# 3S_10A_BMS.net
KiCad netlist of a schematic drawn in EasyEDA
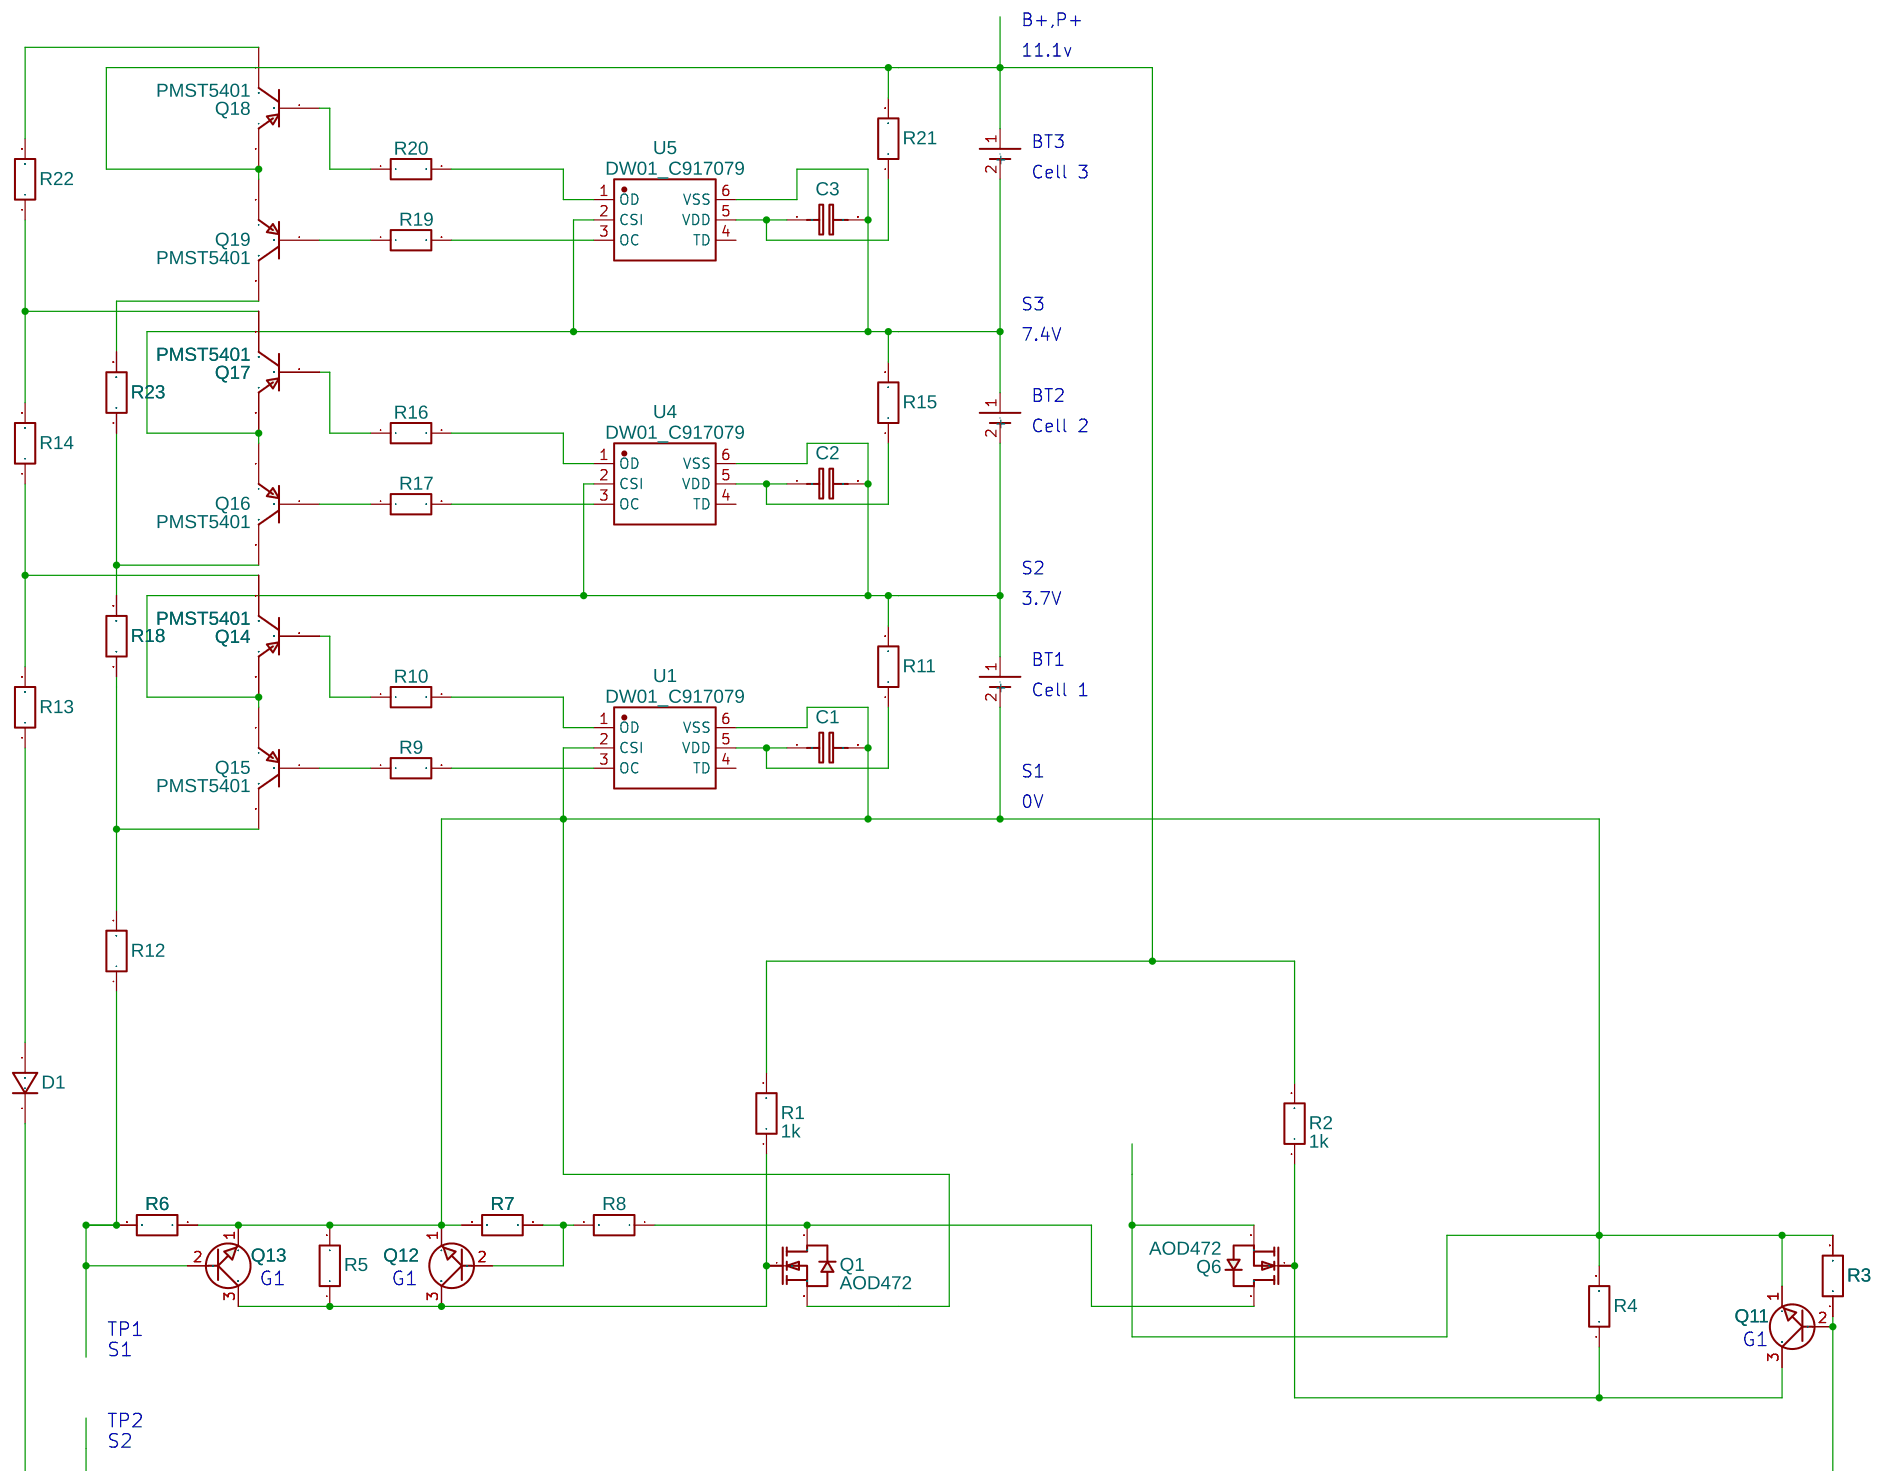
[diagram p0: 3s 10A Schematic]
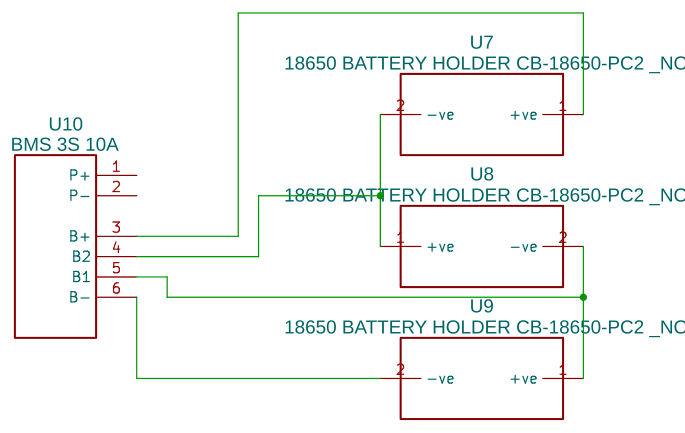
[diagram p1: 12v connection]

(export (version "E")
  (design (tool "Eeschema 10.0.6"))
  (components
    (comp (ref "C1") (value "0.1u") (libsource (lib "") (part "C_0603_EU")))
    (comp (ref "C2") (value "0.1u") (libsource (lib "") (part "C_0603_EU")))
    (comp (ref "C3") (value "0.1u") (libsource (lib "") (part "C_0603_EU")))
    (comp (ref "D1")
      (value "1N4007W")
      (fields (field (name "BOM_Supplier Part") "C328592"))
      (libsource (lib "") (part "1N4007W"))
    )
    (comp (ref "Q1")
      (value "AOD472")
      (fields (field (name "BOM_Supplier Part") "C693172"))
      (libsource (lib "") (part "AOD472"))
    )
    (comp (ref "Q6")
      (value "AOD472")
      (fields (field (name "BOM_Supplier Part") "C693172"))
      (libsource (lib "") (part "AOD472_1"))
    )
    (comp (ref "Q11") (value "2N2222") (libsource (lib "") (part "2N2222_1")))
    (comp (ref "Q12") (value "2N2222") (libsource (lib "") (part "2N2222_1")))
    (comp (ref "Q13") (value "2N2222") (libsource (lib "") (part "2N2222")))
    (comp (ref "Q14") (value "PMST5401") (libsource (lib "") (part "PMST5401")))
    (comp (ref "Q15") (value "PMST5401") (libsource (lib "") (part "PMST5401_1")))
    (comp (ref "Q16") (value "PMST5401") (libsource (lib "") (part "PMST5401_1")))
    (comp (ref "Q17") (value "PMST5401") (libsource (lib "") (part "PMST5401")))
    (comp (ref "Q18") (value "PMST5401") (libsource (lib "") (part "PMST5401")))
    (comp (ref "Q19") (value "PMST5401") (libsource (lib "") (part "PMST5401_1")))
    (comp (ref "R1") (value "1k") (libsource (lib "") (part "R_0603_EU")))
    (comp (ref "R2") (value "1k") (libsource (lib "") (part "R_0603_EU")))
    (comp (ref "R3") (value "1k") (libsource (lib "") (part "R_0603_EU")))
    (comp (ref "R4") (value "1k") (libsource (lib "") (part "R_0603_EU")))
    (comp (ref "R5") (value "1k") (libsource (lib "") (part "R_0603_EU")))
    (comp (ref "R6") (value "1k") (libsource (lib "") (part "R_0603_EU_1")))
    (comp (ref "R7") (value "1k") (libsource (lib "") (part "R_0603_EU_1")))
    (comp (ref "R8") (value "1k") (libsource (lib "") (part "R_0603_EU_1")))
    (comp (ref "R9") (value "1k") (libsource (lib "") (part "R_0603_EU_2")))
    (comp (ref "R10") (value "1k") (libsource (lib "") (part "R_0603_EU_2")))
    (comp (ref "R11") (value "1k") (libsource (lib "") (part "R_0603_EU")))
    (comp (ref "R12") (value "1k") (libsource (lib "") (part "R_0603_EU")))
    (comp (ref "R13") (value "1k") (libsource (lib "") (part "R_0603_EU")))
    (comp (ref "R14") (value "1k") (libsource (lib "") (part "R_0603_EU")))
    (comp (ref "R15") (value "1k") (libsource (lib "") (part "R_0603_EU")))
    (comp (ref "R16") (value "1k") (libsource (lib "") (part "R_0603_EU_2")))
    (comp (ref "R17") (value "1k") (libsource (lib "") (part "R_0603_EU_2")))
    (comp (ref "R18") (value "1k") (libsource (lib "") (part "R_0603_EU")))
    (comp (ref "R19") (value "1k") (libsource (lib "") (part "R_0603_EU_2")))
    (comp (ref "R20") (value "1k") (libsource (lib "") (part "R_0603_EU_2")))
    (comp (ref "R21") (value "1k") (libsource (lib "") (part "R_0603_EU")))
    (comp (ref "R22") (value "1k") (libsource (lib "") (part "R_0603_EU")))
    (comp (ref "R23") (value "1k") (libsource (lib "") (part "R_0603_EU")))
    (comp (ref "U1")
      (value "DW01_C917079")
      (fields (field (name "BOM_Manufacturer Part") "DW01") (field (name "BOM_Supplier Part") "C917079"))
      (libsource (lib "") (part "DW01_C917079"))
    )
    (comp (ref "U2") (value "Li-ion battery") (libsource (lib "") (part "Li-ion battery")))
    (comp (ref "U3") (value "Li-ion battery") (libsource (lib "") (part "Li-ion battery")))
    (comp (ref "U4")
      (value "DW01_C917079")
      (fields (field (name "BOM_Manufacturer Part") "DW01") (field (name "BOM_Supplier Part") "C917079"))
      (libsource (lib "") (part "DW01_C917079"))
    )
    (comp (ref "U5")
      (value "DW01_C917079")
      (fields (field (name "BOM_Manufacturer Part") "DW01") (field (name "BOM_Supplier Part") "C917079"))
      (libsource (lib "") (part "DW01_C917079"))
    )
    (comp (ref "U6") (value "Li-ion battery") (libsource (lib "") (part "Li-ion battery")))
    (comp (ref "U7")
      (value "18650 BATTERY HOLDER CB-18650-PC2 _NOTEMP COPY")
      (libsource (lib "") (part "18650 BATTERY HOLDER CB-18650-PC2 _NOTEMP COPY_1"))
    )
    (comp (ref "U8")
      (value "18650 BATTERY HOLDER CB-18650-PC2 _NOTEMP COPY")
      (libsource (lib "") (part "18650 BATTERY HOLDER CB-18650-PC2 _NOTEMP COPY"))
    )
    (comp (ref "U9")
      (value "18650 BATTERY HOLDER CB-18650-PC2 _NOTEMP COPY")
      (libsource (lib "") (part "18650 BATTERY HOLDER CB-18650-PC2 _NOTEMP COPY_1"))
    )
    (comp (ref "U10") (value "BMS 3S 10A") (libsource (lib "") (part "BMS 3S 10A")))
  )
  (nets
    (net (code "1") (name "Net-(D1-Pad2)") (class "Default")
      (node (ref "D1") (pin "2") (pinfunction "2_2") (pintype "unspecified"))
      (node (ref "R13") (pin "1") (pinfunction "1_1") (pintype "unspecified"))
    )
    (net (code "2") (name "Net-(Q1-D)") (class "Default")
      (node (ref "Q1") (pin "2") (pinfunction "D_2") (pintype "unspecified"))
      (node (ref "Q6") (pin "2") (pinfunction "D_2") (pintype "unspecified"))
      (node (ref "R8") (pin "1") (pinfunction "1_1") (pintype "unspecified"))
    )
    (net (code "3") (name "Net-(Q1-G)") (class "Default")
      (node (ref "Q1") (pin "1") (pinfunction "G_1") (pintype "unspecified"))
      (node (ref "Q12") (pin "3") (pinfunction "C_3") (pintype "unspecified"))
      (node (ref "Q13") (pin "3") (pinfunction "C_3") (pintype "unspecified"))
      (node (ref "R1") (pin "1") (pinfunction "1_1") (pintype "unspecified"))
      (node (ref "R5") (pin "1") (pinfunction "1_1") (pintype "unspecified"))
    )
    (net (code "4") (name "Net-(Q1-S)") (class "Default")
      (node (ref "C1") (pin "2") (pinfunction "2_2") (pintype "unspecified"))
      (node (ref "Q1") (pin "3") (pinfunction "S_3") (pintype "unspecified"))
      (node (ref "Q11") (pin "1") (pinfunction "E_1") (pintype "unspecified"))
      (node (ref "Q12") (pin "1") (pinfunction "E_1") (pintype "unspecified"))
      (node (ref "Q13") (pin "1") (pinfunction "E_1") (pintype "unspecified"))
      (node (ref "Q6") (pin "3") (pinfunction "S_3") (pintype "unspecified"))
      (node (ref "R3") (pin "2") (pinfunction "2_2") (pintype "unspecified"))
      (node (ref "R4") (pin "2") (pinfunction "2_2") (pintype "unspecified"))
      (node (ref "R5") (pin "2") (pinfunction "2_2") (pintype "unspecified"))
      (node (ref "R6") (pin "1") (pinfunction "1_1") (pintype "unspecified"))
      (node (ref "R7") (pin "2") (pinfunction "2_2") (pintype "unspecified"))
      (node (ref "U1") (pin "2") (pinfunction "CSI_2") (pintype "unspecified"))
      (node (ref "U1") (pin "6") (pinfunction "VSS_6") (pintype "unspecified"))
      (node (ref "U2") (pin "2") (pinfunction "-_2") (pintype "unspecified"))
    )
    (net (code "5") (name "Net-(Q11-B)") (class "Default")
      (node (ref "D1") (pin "1") (pinfunction "1_1") (pintype "unspecified"))
      (node (ref "Q11") (pin "2") (pinfunction "B_2") (pintype "input"))
      (node (ref "R3") (pin "1") (pinfunction "1_1") (pintype "unspecified"))
    )
    (net (code "6") (name "Net-(Q11-C)") (class "Default")
      (node (ref "Q11") (pin "3") (pinfunction "C_3") (pintype "unspecified"))
      (node (ref "Q6") (pin "1") (pinfunction "G_1") (pintype "unspecified"))
      (node (ref "R2") (pin "1") (pinfunction "1_1") (pintype "unspecified"))
      (node (ref "R4") (pin "1") (pinfunction "1_1") (pintype "unspecified"))
    )
    (net (code "7") (name "Net-(Q12-B)") (class "Default")
      (node (ref "Q12") (pin "2") (pinfunction "B_2") (pintype "input"))
      (node (ref "R7") (pin "1") (pinfunction "1_1") (pintype "unspecified"))
      (node (ref "R8") (pin "2") (pinfunction "2_2") (pintype "unspecified"))
    )
    (net (code "8") (name "Net-(Q13-B)") (class "Default")
      (node (ref "Q13") (pin "2") (pinfunction "B_2") (pintype "input"))
      (node (ref "R12") (pin "1") (pinfunction "1_1") (pintype "unspecified"))
      (node (ref "R6") (pin "2") (pinfunction "2_2") (pintype "unspecified"))
    )
    (net (code "9") (name "Net-(Q14-B)") (class "Default")
      (node (ref "Q14") (pin "1") (pinfunction "B_1") (pintype "unspecified"))
      (node (ref "R10") (pin "1") (pinfunction "1_1") (pintype "unspecified"))
    )
    (net (code "10") (name "Net-(Q14-C)") (class "Default")
      (node (ref "Q14") (pin "3") (pinfunction "C_3") (pintype "unspecified"))
      (node (ref "R13") (pin "2") (pinfunction "2_2") (pintype "unspecified"))
      (node (ref "R14") (pin "1") (pinfunction "1_1") (pintype "unspecified"))
    )
    (net (code "11") (name "Net-(Q14-E)") (class "Default")
      (node (ref "C2") (pin "2") (pinfunction "2_2") (pintype "unspecified"))
      (node (ref "Q14") (pin "2") (pinfunction "E_2") (pintype "unspecified"))
      (node (ref "Q15") (pin "2") (pinfunction "E_2") (pintype "unspecified"))
      (node (ref "R11") (pin "2") (pinfunction "2_2") (pintype "unspecified"))
      (node (ref "U2") (pin "1") (pinfunction "+_1") (pintype "unspecified"))
      (node (ref "U3") (pin "2") (pinfunction "-_2") (pintype "unspecified"))
      (node (ref "U4") (pin "2") (pinfunction "CSI_2") (pintype "unspecified"))
      (node (ref "U4") (pin "6") (pinfunction "VSS_6") (pintype "unspecified"))
    )
    (net (code "12") (name "Net-(Q15-B)") (class "Default")
      (node (ref "Q15") (pin "1") (pinfunction "B_1") (pintype "unspecified"))
      (node (ref "R9") (pin "1") (pinfunction "1_1") (pintype "unspecified"))
    )
    (net (code "13") (name "Net-(Q15-C)") (class "Default")
      (node (ref "Q15") (pin "3") (pinfunction "C_3") (pintype "unspecified"))
      (node (ref "R12") (pin "2") (pinfunction "2_2") (pintype "unspecified"))
      (node (ref "R18") (pin "1") (pinfunction "1_1") (pintype "unspecified"))
    )
    (net (code "14") (name "Net-(Q16-B)") (class "Default")
      (node (ref "Q16") (pin "1") (pinfunction "B_1") (pintype "unspecified"))
      (node (ref "R17") (pin "1") (pinfunction "1_1") (pintype "unspecified"))
    )
    (net (code "15") (name "Net-(Q16-C)") (class "Default")
      (node (ref "Q16") (pin "3") (pinfunction "C_3") (pintype "unspecified"))
      (node (ref "R18") (pin "2") (pinfunction "2_2") (pintype "unspecified"))
      (node (ref "R23") (pin "1") (pinfunction "1_1") (pintype "unspecified"))
    )
    (net (code "16") (name "Net-(Q16-E)") (class "Default")
      (node (ref "C3") (pin "2") (pinfunction "2_2") (pintype "unspecified"))
      (node (ref "Q16") (pin "2") (pinfunction "E_2") (pintype "unspecified"))
      (node (ref "Q17") (pin "2") (pinfunction "E_2") (pintype "unspecified"))
      (node (ref "R15") (pin "2") (pinfunction "2_2") (pintype "unspecified"))
      (node (ref "U3") (pin "1") (pinfunction "+_1") (pintype "unspecified"))
      (node (ref "U5") (pin "2") (pinfunction "CSI_2") (pintype "unspecified"))
      (node (ref "U5") (pin "6") (pinfunction "VSS_6") (pintype "unspecified"))
      (node (ref "U6") (pin "2") (pinfunction "-_2") (pintype "unspecified"))
    )
    (net (code "17") (name "Net-(Q17-B)") (class "Default")
      (node (ref "Q17") (pin "1") (pinfunction "B_1") (pintype "unspecified"))
      (node (ref "R16") (pin "1") (pinfunction "1_1") (pintype "unspecified"))
    )
    (net (code "18") (name "Net-(Q17-C)") (class "Default")
      (node (ref "Q17") (pin "3") (pinfunction "C_3") (pintype "unspecified"))
      (node (ref "R14") (pin "2") (pinfunction "2_2") (pintype "unspecified"))
      (node (ref "R22") (pin "1") (pinfunction "1_1") (pintype "unspecified"))
    )
    (net (code "19") (name "Net-(Q18-B)") (class "Default")
      (node (ref "Q18") (pin "1") (pinfunction "B_1") (pintype "unspecified"))
      (node (ref "R20") (pin "1") (pinfunction "1_1") (pintype "unspecified"))
    )
    (net (code "20") (name "Net-(Q18-C)") (class "Default")
      (node (ref "Q18") (pin "3") (pinfunction "C_3") (pintype "unspecified"))
      (node (ref "R22") (pin "2") (pinfunction "2_2") (pintype "unspecified"))
    )
    (net (code "21") (name "Net-(Q18-E)") (class "Default")
      (node (ref "Q18") (pin "2") (pinfunction "E_2") (pintype "unspecified"))
      (node (ref "Q19") (pin "2") (pinfunction "E_2") (pintype "unspecified"))
      (node (ref "R1") (pin "2") (pinfunction "2_2") (pintype "unspecified"))
      (node (ref "R2") (pin "2") (pinfunction "2_2") (pintype "unspecified"))
      (node (ref "R21") (pin "2") (pinfunction "2_2") (pintype "unspecified"))
      (node (ref "U6") (pin "1") (pinfunction "+_1") (pintype "unspecified"))
    )
    (net (code "22") (name "Net-(Q19-B)") (class "Default")
      (node (ref "Q19") (pin "1") (pinfunction "B_1") (pintype "unspecified"))
      (node (ref "R19") (pin "1") (pinfunction "1_1") (pintype "unspecified"))
    )
    (net (code "23") (name "Net-(Q19-C)") (class "Default")
      (node (ref "Q19") (pin "3") (pinfunction "C_3") (pintype "unspecified"))
      (node (ref "R23") (pin "2") (pinfunction "2_2") (pintype "unspecified"))
    )
    (net (code "24") (name "Net-(U1-OC)") (class "Default")
      (node (ref "R9") (pin "2") (pinfunction "2_2") (pintype "unspecified"))
      (node (ref "U1") (pin "3") (pinfunction "OC_3") (pintype "unspecified"))
    )
    (net (code "25") (name "Net-(U1-OD)") (class "Default")
      (node (ref "R10") (pin "2") (pinfunction "2_2") (pintype "unspecified"))
      (node (ref "U1") (pin "1") (pinfunction "OD_1") (pintype "unspecified"))
    )
    (net (code "26") (name "Net-(U1-VDD)") (class "Default")
      (node (ref "C1") (pin "1") (pinfunction "1_1") (pintype "unspecified"))
      (node (ref "R11") (pin "1") (pinfunction "1_1") (pintype "unspecified"))
      (node (ref "U1") (pin "5") (pinfunction "VDD_5") (pintype "unspecified"))
    )
    (net (code "27") (name "Net-(U4-OC)") (class "Default")
      (node (ref "R17") (pin "2") (pinfunction "2_2") (pintype "unspecified"))
      (node (ref "U4") (pin "3") (pinfunction "OC_3") (pintype "unspecified"))
    )
    (net (code "28") (name "Net-(U4-OD)") (class "Default")
      (node (ref "R16") (pin "2") (pinfunction "2_2") (pintype "unspecified"))
      (node (ref "U4") (pin "1") (pinfunction "OD_1") (pintype "unspecified"))
    )
    (net (code "29") (name "Net-(U4-VDD)") (class "Default")
      (node (ref "C2") (pin "1") (pinfunction "1_1") (pintype "unspecified"))
      (node (ref "R15") (pin "1") (pinfunction "1_1") (pintype "unspecified"))
      (node (ref "U4") (pin "5") (pinfunction "VDD_5") (pintype "unspecified"))
    )
    (net (code "30") (name "Net-(U5-OC)") (class "Default")
      (node (ref "R19") (pin "2") (pinfunction "2_2") (pintype "unspecified"))
      (node (ref "U5") (pin "3") (pinfunction "OC_3") (pintype "unspecified"))
    )
    (net (code "31") (name "Net-(U5-OD)") (class "Default")
      (node (ref "R20") (pin "2") (pinfunction "2_2") (pintype "unspecified"))
      (node (ref "U5") (pin "1") (pinfunction "OD_1") (pintype "unspecified"))
    )
    (net (code "32") (name "Net-(U5-VDD)") (class "Default")
      (node (ref "C3") (pin "1") (pinfunction "1_1") (pintype "unspecified"))
      (node (ref "R21") (pin "1") (pinfunction "1_1") (pintype "unspecified"))
      (node (ref "U5") (pin "5") (pinfunction "VDD_5") (pintype "unspecified"))
    )
    (net (code "33") (name "Net-(U10-B+)") (class "Default")
      (node (ref "U10") (pin "3") (pinfunction "B+_3") (pintype "unspecified"))
      (node (ref "U7") (pin "1") (pinfunction "+ve_1") (pintype "passive"))
    )
    (net (code "34") (name "Net-(U10-B-)") (class "Default")
      (node (ref "U10") (pin "6") (pinfunction "B-_6") (pintype "unspecified"))
      (node (ref "U9") (pin "2") (pinfunction "-ve_2") (pintype "passive"))
    )
    (net (code "35") (name "Net-(U10-B1)") (class "Default")
      (node (ref "U10") (pin "5") (pinfunction "B1_5") (pintype "unspecified"))
      (node (ref "U8") (pin "2") (pinfunction "-ve_2") (pintype "passive"))
      (node (ref "U9") (pin "1") (pinfunction "+ve_1") (pintype "passive"))
    )
    (net (code "36") (name "Net-(U10-B2)") (class "Default")
      (node (ref "U10") (pin "4") (pinfunction "B2_4") (pintype "unspecified"))
      (node (ref "U7") (pin "2") (pinfunction "-ve_2") (pintype "passive"))
      (node (ref "U8") (pin "1") (pinfunction "+ve_1") (pintype "passive"))
    )
    (net (code "37") (name "unconnected-(U1-TD-Pad4)") (class "Default")
      (node (ref "U1") (pin "4") (pinfunction "TD_4") (pintype "unspecified"))
    )
    (net (code "38") (name "unconnected-(U4-TD-Pad4)") (class "Default")
      (node (ref "U4") (pin "4") (pinfunction "TD_4") (pintype "unspecified"))
    )
    (net (code "39") (name "unconnected-(U5-TD-Pad4)") (class "Default")
      (node (ref "U5") (pin "4") (pinfunction "TD_4") (pintype "unspecified"))
    )
    (net (code "40") (name "unconnected-(U10-P+-Pad1)") (class "Default")
      (node (ref "U10") (pin "1") (pinfunction "P+_1") (pintype "unspecified"))
    )
    (net (code "41") (name "unconnected-(U10-P--Pad2)") (class "Default")
      (node (ref "U10") (pin "2") (pinfunction "P-_2") (pintype "unspecified"))
    )
  )
)
